# Lightpack7_0L.net
KiCad netlist of a schematic drawn in EAGLE
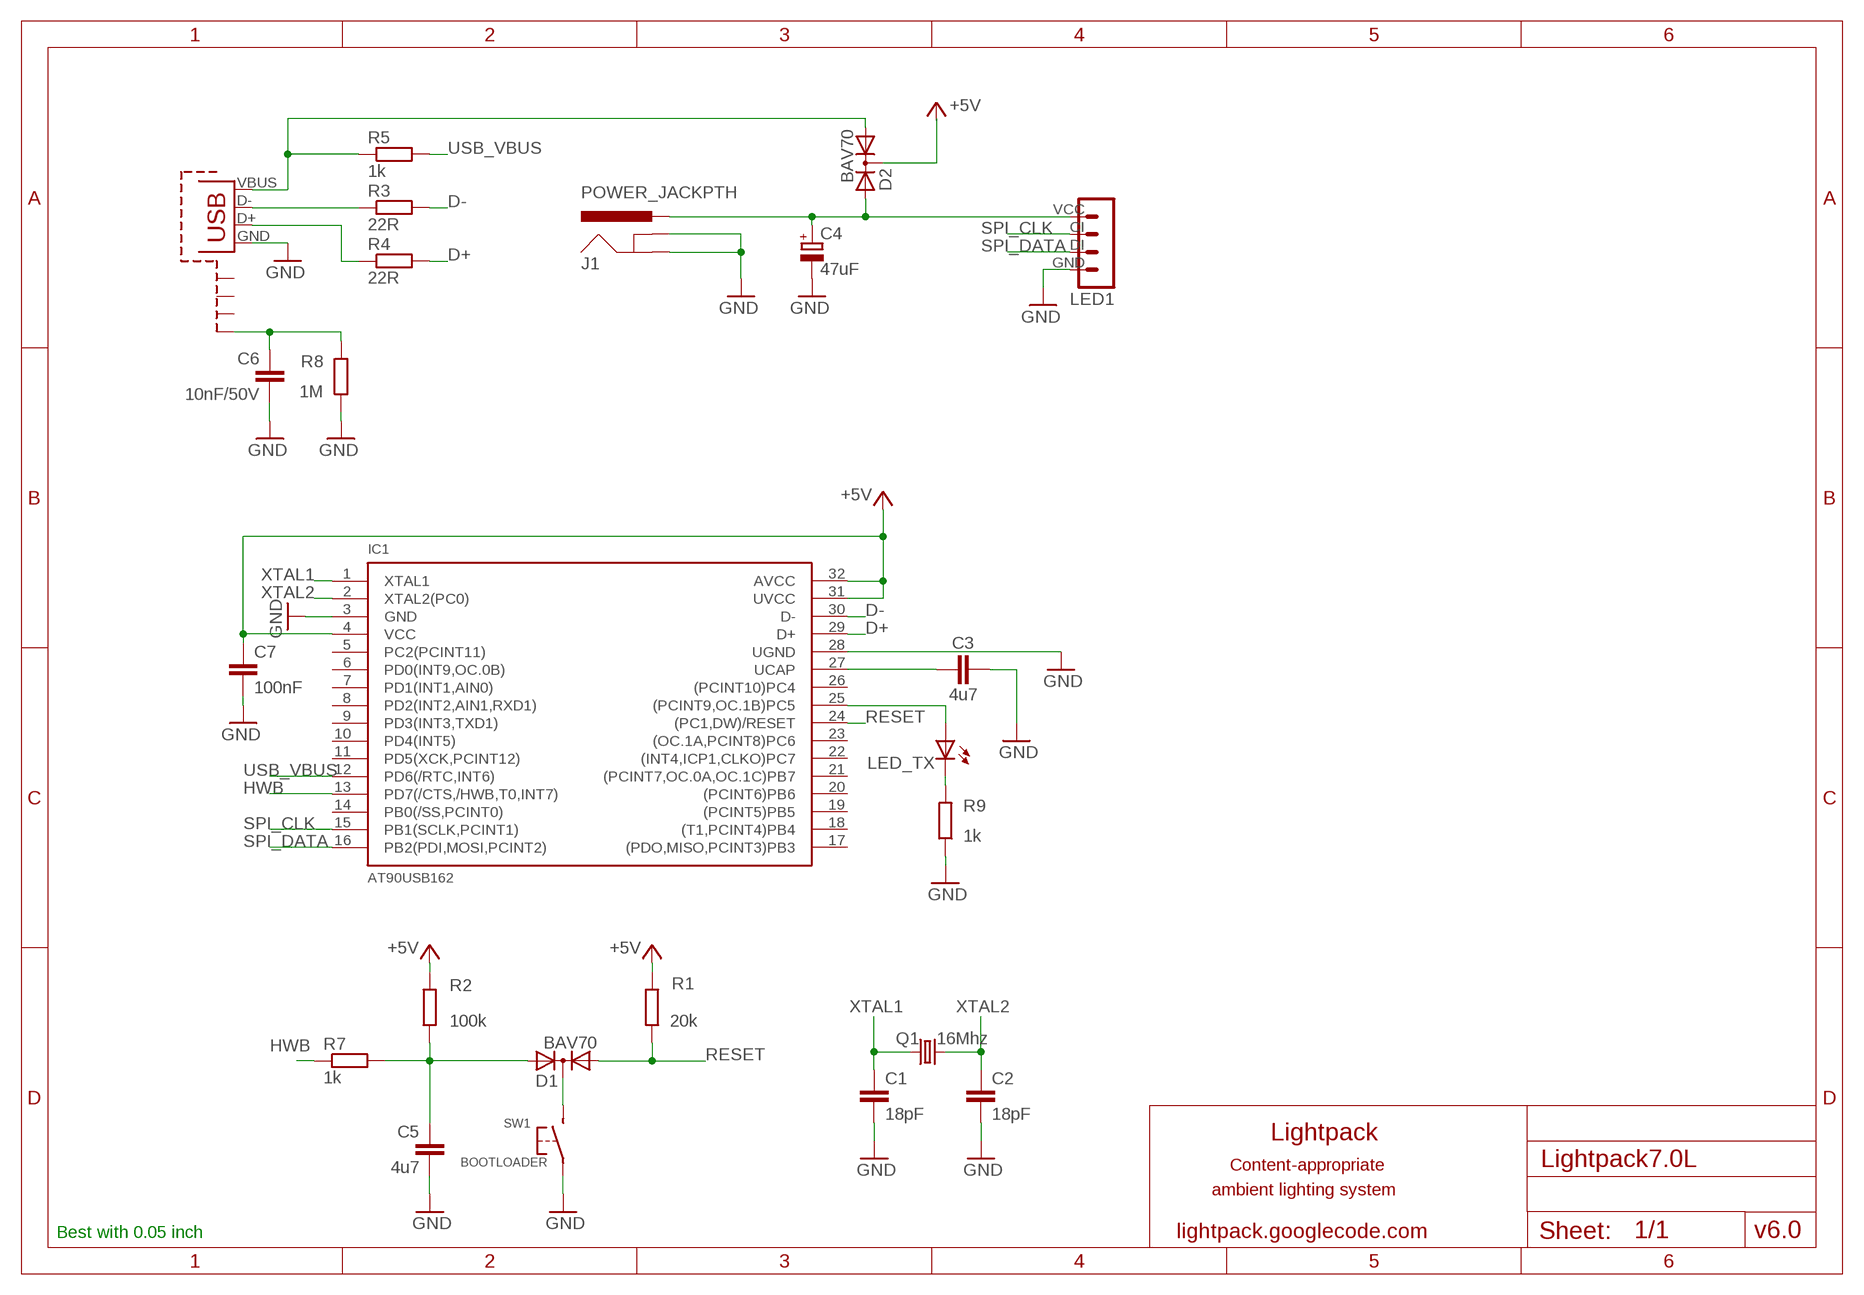
[diagram p0: schematic, sheet 1]

(export (version "E")
  (design (tool "Eeschema 10.0.6"))
  (components
    (comp (ref "C1")
      (value "18pF")
      (footprint "eagle-import:C1206")
      (libsource (lib "eagle-import") (part "C-EUC1206"))
    )
    (comp (ref "C2")
      (value "18pF")
      (footprint "eagle-import:C1206")
      (libsource (lib "eagle-import") (part "C-EUC1206"))
    )
    (comp (ref "C3")
      (value "4u7")
      (footprint "eagle-import:C1206")
      (libsource (lib "eagle-import") (part "C-EUC1206"))
    )
    (comp (ref "C4")
      (value "47uF")
      (footprint "eagle-import:D_7343-31W")
      (libsource (lib "eagle-import") (part "CPOL-EUD/7343-31W"))
    )
    (comp (ref "C5")
      (value "4u7")
      (footprint "eagle-import:C1206")
      (libsource (lib "eagle-import") (part "C-EUC1206"))
    )
    (comp (ref "C6")
      (value "10nF/50V")
      (footprint "eagle-import:C1206")
      (libsource (lib "eagle-import") (part "C-EUC1206"))
    )
    (comp (ref "C7")
      (value "100nF")
      (footprint "eagle-import:C1206")
      (libsource (lib "eagle-import") (part "C-EUC1206"))
    )
    (comp (ref "D1")
      (value "BAV70")
      (footprint "eagle-import:SOT23")
      (libsource (lib "eagle-import") (part "DIODE-2AC|CASOT23"))
    )
    (comp (ref "D2")
      (value "BAV70")
      (footprint "eagle-import:SOT23")
      (libsource (lib "eagle-import") (part "DIODE-2AC|CASOT23"))
    )
    (comp (ref "IC1")
      (value "AT90USB162")
      (footprint "eagle-import:TQFP32")
      (libsource (lib "eagle-import") (part "AT90USB162"))
    )
    (comp (ref "J1")
      (value "POWER_JACKPTH")
      (footprint "eagle-import:POWER_JACK_PTH")
      (libsource (lib "eagle-import") (part "POWER_JACKPTH"))
    )
    (comp (ref "LED1")
      (value "RGB_LED_STRIP")
      (footprint "eagle-import:MA04-1")
      (libsource (lib "eagle-import") (part "RGB_LED_STRIP"))
    )
    (comp (ref "LED_TX")
      (value "GREEN")
      (footprint "eagle-import:CHIPLED_0805")
      (libsource (lib "eagle-import") (part "LEDCHIPLED_0805"))
    )
    (comp (ref "Q1")
      (value "16Mhz")
      (footprint "eagle-import:HC49UP")
      (libsource (lib "eagle-import") (part "CRYSTALHC49UP"))
    )
    (comp (ref "R1")
      (value "20k")
      (footprint "eagle-import:R1206")
      (libsource (lib "eagle-import") (part "R-EU_R1206"))
    )
    (comp (ref "R2")
      (value "100k")
      (footprint "eagle-import:R1206")
      (libsource (lib "eagle-import") (part "R-EU_R1206_2"))
    )
    (comp (ref "R3")
      (value "22R")
      (footprint "eagle-import:R1206")
      (libsource (lib "eagle-import") (part "rcl_R-EU_R1206"))
    )
    (comp (ref "R4")
      (value "22R")
      (footprint "eagle-import:R1206")
      (libsource (lib "eagle-import") (part "rcl_R-EU_R1206"))
    )
    (comp (ref "R5")
      (value "1k")
      (footprint "eagle-import:R1206")
      (libsource (lib "eagle-import") (part "rcl_R-EU_R1206"))
    )
    (comp (ref "R7")
      (value "1k")
      (footprint "eagle-import:R1206")
      (libsource (lib "eagle-import") (part "rcl_R-EU_R1206"))
    )
    (comp (ref "R8")
      (value "1M")
      (footprint "eagle-import:R1206")
      (libsource (lib "eagle-import") (part "rcl_R-EU_R1206"))
    )
    (comp (ref "R9")
      (value "1k")
      (footprint "eagle-import:R1206")
      (libsource (lib "eagle-import") (part "rcl_R-EU_R1206"))
    )
    (comp (ref "SW1")
      (value "BOOTLOADER")
      (footprint "eagle-import:BUTTON-SMD")
      (libsource (lib "eagle-import") (part "BUTTON"))
    )
    (comp (ref "X1")
      (value "USB-MB-S")
      (footprint "eagle-import:USB-MB-S")
      (libsource (lib "eagle-import") (part "USB-MB-S"))
    )
  )
  (nets
    (net (code "1") (name "+5V") (class "Default")
      (node (ref "C7") (pin "1") (pinfunction "1_1") (pintype "passive"))
      (node (ref "IC1") (pin "31") (pinfunction "UVCC_31") (pintype "bidirectional"))
      (node (ref "IC1") (pin "32") (pinfunction "AVCC_32") (pintype "bidirectional"))
      (node (ref "IC1") (pin "4") (pinfunction "VCC_4") (pintype "bidirectional"))
      (node (ref "R1") (pin "2") (pinfunction "2_2") (pintype "passive"))
      (node (ref "R2") (pin "1") (pinfunction "2_1") (pintype "passive"))
    )
    (net (code "2") (name "/D+") (class "Default")
      (node (ref "IC1") (pin "29") (pinfunction "D+_29") (pintype "bidirectional"))
      (node (ref "R4") (pin "2") (pinfunction "2_2") (pintype "passive"))
    )
    (net (code "3") (name "/D-") (class "Default")
      (node (ref "IC1") (pin "30") (pinfunction "D-_30") (pintype "bidirectional"))
      (node (ref "R3") (pin "2") (pinfunction "2_2") (pintype "passive"))
    )
    (net (code "4") (name "/HWB") (class "Default")
      (node (ref "IC1") (pin "13") (pinfunction "PD7(/CTS,/HWB,T0,INT7)_13") (pintype "bidirectional"))
      (node (ref "R7") (pin "1") (pinfunction "1_1") (pintype "passive"))
    )
    (net (code "5") (name "/RESET") (class "Default")
      (node (ref "D1") (pin "1") (pinfunction "A1_1") (pintype "passive"))
      (node (ref "IC1") (pin "24") (pinfunction "(PC1,DW)/RESET_24") (pintype "bidirectional"))
      (node (ref "R1") (pin "1") (pinfunction "1_1") (pintype "passive"))
    )
    (net (code "6") (name "/SPI_CLK") (class "Default")
      (node (ref "IC1") (pin "15") (pinfunction "PB1(SCLK,PCINT1)_15") (pintype "bidirectional"))
      (node (ref "LED1") (pin "CI") (pinfunction "CI_CI") (pintype "passive"))
    )
    (net (code "7") (name "/SPI_DATA") (class "Default")
      (node (ref "IC1") (pin "16") (pinfunction "PB2(PDI,MOSI,PCINT2)_16") (pintype "bidirectional"))
      (node (ref "LED1") (pin "DI") (pinfunction "DI_DI") (pintype "passive"))
    )
    (net (code "8") (name "/USB_VBUS") (class "Default")
      (node (ref "IC1") (pin "12") (pinfunction "PD6(/RTC,INT6)_12") (pintype "bidirectional"))
      (node (ref "R5") (pin "2") (pinfunction "2_2") (pintype "passive"))
    )
    (net (code "9") (name "/XTAL1") (class "Default")
      (node (ref "C1") (pin "1") (pinfunction "1_1") (pintype "passive"))
      (node (ref "IC1") (pin "1") (pinfunction "XTAL1_1") (pintype "bidirectional"))
      (node (ref "Q1") (pin "1") (pinfunction "1_1") (pintype "passive"))
    )
    (net (code "10") (name "/XTAL2") (class "Default")
      (node (ref "C2") (pin "1") (pinfunction "1_1") (pintype "passive"))
      (node (ref "IC1") (pin "2") (pinfunction "XTAL2(PC0)_2") (pintype "bidirectional"))
      (node (ref "Q1") (pin "2") (pinfunction "2_2") (pintype "passive"))
    )
    (net (code "11") (name "GND") (class "Default")
      (node (ref "C1") (pin "2") (pinfunction "2_2") (pintype "passive"))
      (node (ref "C2") (pin "2") (pinfunction "2_2") (pintype "passive"))
      (node (ref "C3") (pin "1") (pinfunction "1_1") (pintype "passive"))
      (node (ref "C4") (pin "-") (pinfunction "-_-") (pintype "passive"))
      (node (ref "C5") (pin "2") (pinfunction "2_2") (pintype "passive"))
      (node (ref "C6") (pin "2") (pinfunction "2_2") (pintype "passive"))
      (node (ref "C7") (pin "2") (pinfunction "2_2") (pintype "passive"))
      (node (ref "IC1") (pin "28") (pinfunction "UGND_28") (pintype "bidirectional"))
      (node (ref "IC1") (pin "3") (pinfunction "GND_3") (pintype "bidirectional"))
      (node (ref "J1") (pin "GND") (pinfunction "GND_GND") (pintype "bidirectional"))
      (node (ref "J1") (pin "GNDBREAK") (pinfunction "GNDBREAK_GNDBREAK") (pintype "bidirectional"))
      (node (ref "LED1") (pin "GND") (pinfunction "GND_GND") (pintype "passive"))
      (node (ref "R8") (pin "1") (pinfunction "1_1") (pintype "passive"))
      (node (ref "R9") (pin "1") (pinfunction "1_1") (pintype "passive"))
      (node (ref "SW1") (pin "1") (pinfunction "1_1") (pintype "passive"))
      (node (ref "X1") (pin "GND") (pinfunction "GND_GND") (pintype "bidirectional"))
    )
    (net (code "12") (name "Net-(C6-Pad1)") (class "Default")
      (node (ref "C6") (pin "1") (pinfunction "1_1") (pintype "passive"))
      (node (ref "R8") (pin "2") (pinfunction "2_2") (pintype "passive"))
      (node (ref "X1") (pin "SHIELD4") (pinfunction "SHIELD4_SHIELD4") (pintype "bidirectional"))
    )
    (net (code "13") (name "Net-(D1-A2)") (class "Default")
      (node (ref "C5") (pin "1") (pinfunction "1_1") (pintype "passive"))
      (node (ref "D1") (pin "2") (pinfunction "A2_2") (pintype "passive"))
      (node (ref "R2") (pin "2") (pinfunction "1_2") (pintype "passive"))
      (node (ref "R7") (pin "2") (pinfunction "2_2") (pintype "passive"))
    )
    (net (code "14") (name "Net-(D1-C)") (class "Default")
      (node (ref "D1") (pin "3") (pinfunction "C_3") (pintype "passive"))
      (node (ref "SW1") (pin "2") (pinfunction "2_2") (pintype "passive"))
    )
    (net (code "15") (name "Net-(D2-A1)") (class "Default")
      (node (ref "D2") (pin "1") (pinfunction "A1_1") (pintype "passive"))
      (node (ref "R5") (pin "1") (pinfunction "1_1") (pintype "passive"))
      (node (ref "X1") (pin "VBUS") (pinfunction "VBUS_VBUS") (pintype "bidirectional"))
    )
    (net (code "16") (name "Net-(D2-A2)") (class "Default")
      (node (ref "C4") (pin "+") (pinfunction "+_+") (pintype "passive"))
      (node (ref "D2") (pin "2") (pinfunction "A2_2") (pintype "passive"))
      (node (ref "J1") (pin "PWR") (pinfunction "PWR_PWR") (pintype "bidirectional"))
      (node (ref "LED1") (pin "VCC") (pinfunction "VCC_VCC") (pintype "passive"))
    )
    (net (code "17") (name "Net-(IC1-(PCINT9,OC.1B)PC5)") (class "Default")
      (node (ref "IC1") (pin "25") (pinfunction "(PCINT9,OC.1B)PC5_25") (pintype "bidirectional"))
      (node (ref "LED_TX") (pin "A") (pinfunction "A_A") (pintype "passive"))
    )
    (net (code "18") (name "Net-(IC1-UCAP)") (class "Default")
      (node (ref "C3") (pin "2") (pinfunction "2_2") (pintype "passive"))
      (node (ref "IC1") (pin "27") (pinfunction "UCAP_27") (pintype "bidirectional"))
    )
    (net (code "19") (name "Net-(LED_TX-PadC)") (class "Default")
      (node (ref "LED_TX") (pin "C") (pinfunction "C_C") (pintype "passive"))
      (node (ref "R9") (pin "2") (pinfunction "2_2") (pintype "passive"))
    )
    (net (code "20") (name "Net-(R3-Pad1)") (class "Default")
      (node (ref "R3") (pin "1") (pinfunction "1_1") (pintype "passive"))
      (node (ref "X1") (pin "D-") (pinfunction "D-_D-") (pintype "bidirectional"))
    )
    (net (code "21") (name "Net-(R4-Pad1)") (class "Default")
      (node (ref "R4") (pin "1") (pinfunction "1_1") (pintype "passive"))
      (node (ref "X1") (pin "D+") (pinfunction "D+_D+") (pintype "bidirectional"))
    )
    (net (code "22") (name "unconnected-(D2-C-Pad3)") (class "Default")
      (node (ref "D2") (pin "3") (pinfunction "C_3") (pintype "passive"))
    )
    (net (code "23") (name "unconnected-(IC1-(INT4,ICP1,CLKO)PC7-Pad22)") (class "Default")
      (node (ref "IC1") (pin "22") (pinfunction "(INT4,ICP1,CLKO)PC7_22") (pintype "bidirectional"))
    )
    (net (code "24") (name "unconnected-(IC1-(OC.1A,PCINT8)PC6-Pad23)") (class "Default")
      (node (ref "IC1") (pin "23") (pinfunction "(OC.1A,PCINT8)PC6_23") (pintype "bidirectional"))
    )
    (net (code "25") (name "unconnected-(IC1-(PCINT5)PB5-Pad19)") (class "Default")
      (node (ref "IC1") (pin "19") (pinfunction "(PCINT5)PB5_19") (pintype "bidirectional"))
    )
    (net (code "26") (name "unconnected-(IC1-(PCINT6)PB6-Pad20)") (class "Default")
      (node (ref "IC1") (pin "20") (pinfunction "(PCINT6)PB6_20") (pintype "bidirectional"))
    )
    (net (code "27") (name "unconnected-(IC1-(PCINT7,OC.0A,OC.1C)PB7-Pad21)") (class "Default")
      (node (ref "IC1") (pin "21") (pinfunction "(PCINT7,OC.0A,OC.1C)PB7_21") (pintype "bidirectional"))
    )
    (net (code "28") (name "unconnected-(IC1-(PCINT10)PC4-Pad26)") (class "Default")
      (node (ref "IC1") (pin "26") (pinfunction "(PCINT10)PC4_26") (pintype "bidirectional"))
    )
    (net (code "29") (name "unconnected-(IC1-(PDO,MISO,PCINT3)PB3-Pad17)") (class "Default")
      (node (ref "IC1") (pin "17") (pinfunction "(PDO,MISO,PCINT3)PB3_17") (pintype "bidirectional"))
    )
    (net (code "30") (name "unconnected-(IC1-(T1,PCINT4)PB4-Pad18)") (class "Default")
      (node (ref "IC1") (pin "18") (pinfunction "(T1,PCINT4)PB4_18") (pintype "bidirectional"))
    )
    (net (code "31") (name "unconnected-(IC1-PB0({slash}SS,PCINT0)-Pad14)") (class "Default")
      (node (ref "IC1") (pin "14") (pinfunction "PB0(/SS,PCINT0)_14") (pintype "bidirectional"))
    )
    (net (code "32") (name "unconnected-(IC1-PC2(PCINT11)-Pad5)") (class "Default")
      (node (ref "IC1") (pin "5") (pinfunction "PC2(PCINT11)_5") (pintype "bidirectional"))
    )
    (net (code "33") (name "unconnected-(IC1-PD0(INT9,OC.0B)-Pad6)") (class "Default")
      (node (ref "IC1") (pin "6") (pinfunction "PD0(INT9,OC.0B)_6") (pintype "bidirectional"))
    )
    (net (code "34") (name "unconnected-(IC1-PD1(INT1,AIN0)-Pad7)") (class "Default")
      (node (ref "IC1") (pin "7") (pinfunction "PD1(INT1,AIN0)_7") (pintype "bidirectional"))
    )
    (net (code "35") (name "unconnected-(IC1-PD2(INT2,AIN1,RXD1)-Pad8)") (class "Default")
      (node (ref "IC1") (pin "8") (pinfunction "PD2(INT2,AIN1,RXD1)_8") (pintype "bidirectional"))
    )
    (net (code "36") (name "unconnected-(IC1-PD3(INT3,TXD1)-Pad9)") (class "Default")
      (node (ref "IC1") (pin "9") (pinfunction "PD3(INT3,TXD1)_9") (pintype "bidirectional"))
    )
    (net (code "37") (name "unconnected-(IC1-PD4(INT5)-Pad10)") (class "Default")
      (node (ref "IC1") (pin "10") (pinfunction "PD4(INT5)_10") (pintype "bidirectional"))
    )
    (net (code "38") (name "unconnected-(IC1-PD5(XCK,PCINT12)-Pad11)") (class "Default")
      (node (ref "IC1") (pin "11") (pinfunction "PD5(XCK,PCINT12)_11") (pintype "bidirectional"))
    )
    (net (code "39") (name "unconnected-(X1-PadSHIELD1)") (class "Default")
      (node (ref "X1") (pin "SHIELD1") (pinfunction "SHIELD1_SHIELD1") (pintype "bidirectional"))
    )
    (net (code "40") (name "unconnected-(X1-PadSHIELD2)") (class "Default")
      (node (ref "X1") (pin "SHIELD2") (pinfunction "SHIELD2_SHIELD2") (pintype "bidirectional"))
    )
    (net (code "41") (name "unconnected-(X1-PadSHIELD3)") (class "Default")
      (node (ref "X1") (pin "SHIELD3") (pinfunction "SHIELD3_SHIELD3") (pintype "bidirectional"))
    )
  )
)
